# Power_conversion_board.net
KiCad netlist of a schematic drawn in EAGLE
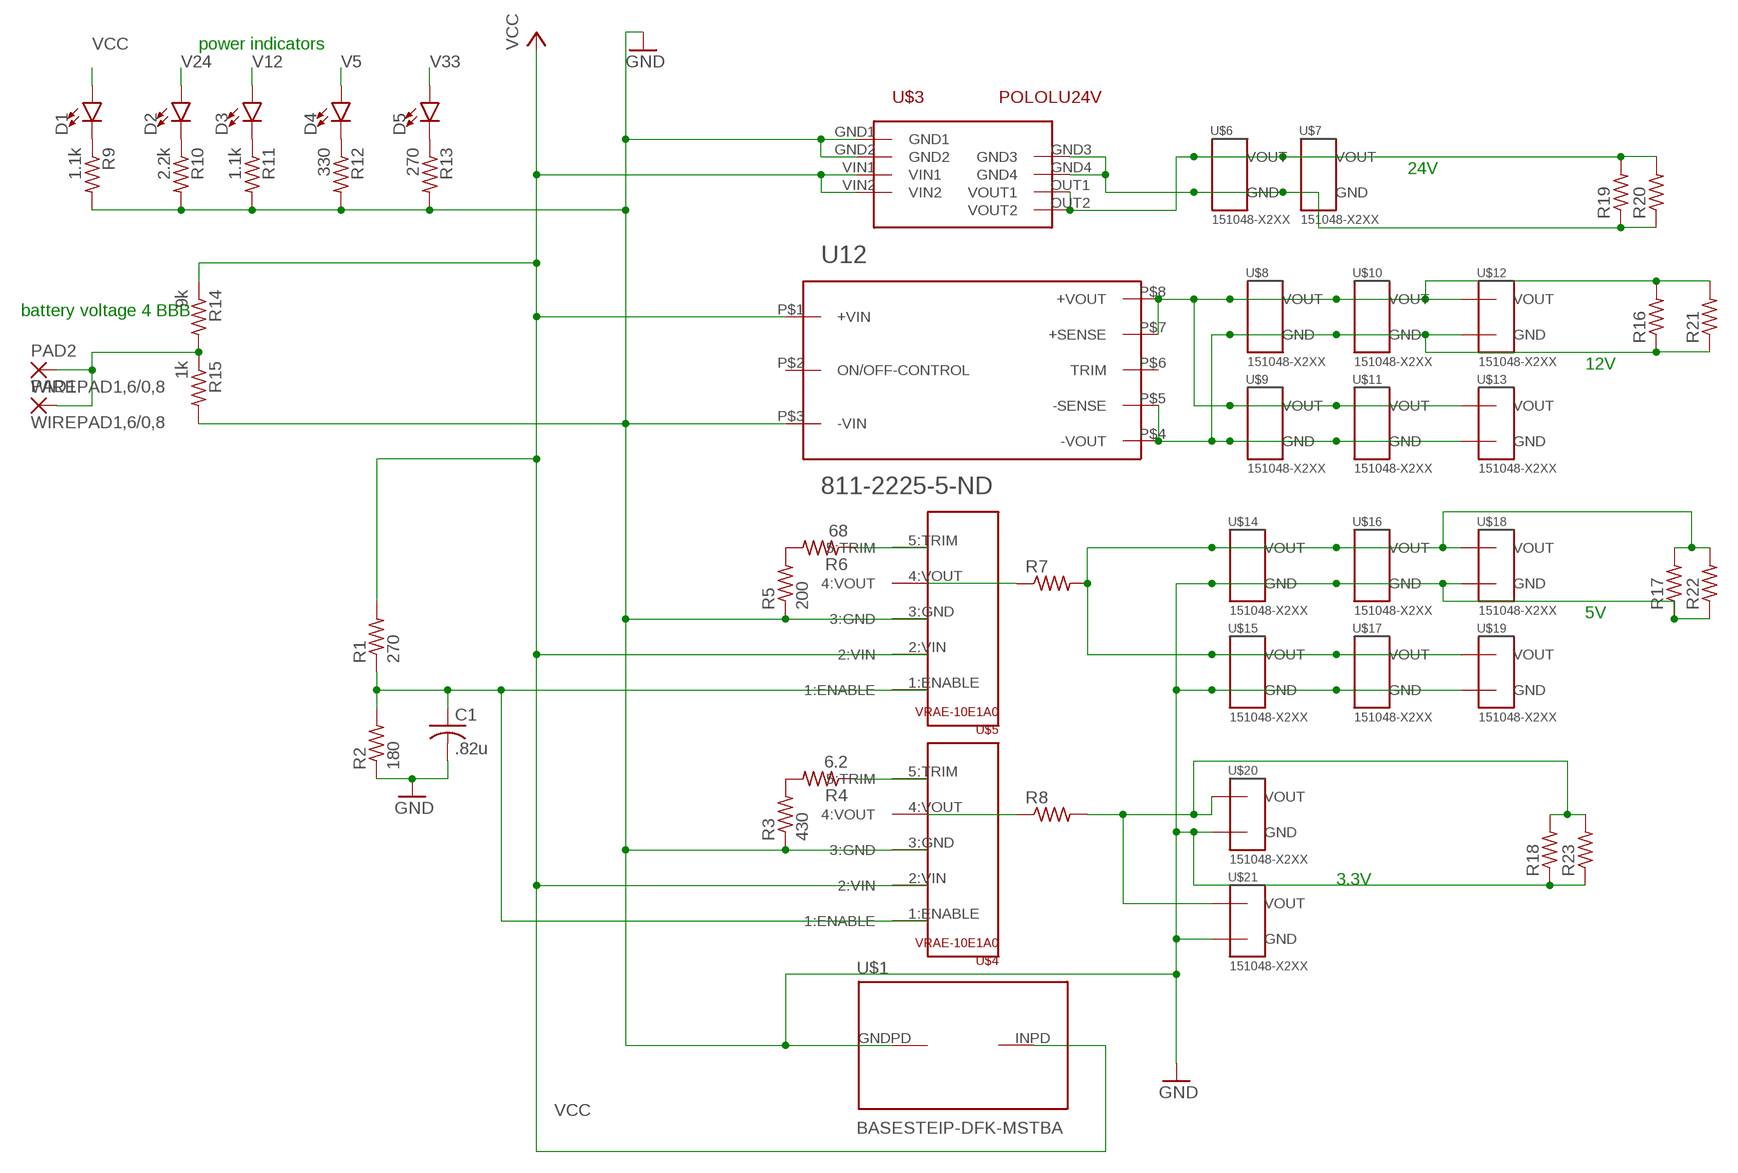
[diagram p0: schematic, sheet 1]

(export (version "E")
  (design (tool "Eeschema 10.0.6"))
  (components
    (comp (ref "C1")
      (value ".82u")
      (footprint "eagle-import:C0603")
      (libsource (lib "eagle-import") (part "C-USC0603"))
    )
    (comp (ref "D1")
      (value "LED5MM")
      (footprint "eagle-import:LED_5MM")
      (libsource (lib "eagle-import") (part "LED5MM"))
    )
    (comp (ref "D2")
      (value "LED5MM")
      (footprint "eagle-import:LED_5MM")
      (libsource (lib "eagle-import") (part "LED5MM"))
    )
    (comp (ref "D3")
      (value "LED5MM")
      (footprint "eagle-import:LED_5MM")
      (libsource (lib "eagle-import") (part "LED5MM"))
    )
    (comp (ref "D4")
      (value "LED5MM")
      (footprint "eagle-import:LED_5MM")
      (libsource (lib "eagle-import") (part "LED5MM"))
    )
    (comp (ref "D5")
      (value "LED5MM")
      (footprint "eagle-import:LED_5MM")
      (libsource (lib "eagle-import") (part "LED5MM"))
    )
    (comp (ref "PAD1")
      (value "WIREPAD1,6/0,8")
      (footprint "eagle-import:1,6_0,8")
      (libsource (lib "eagle-import") (part "WIREPAD1,6/0,8"))
    )
    (comp (ref "PAD2")
      (value "WIREPAD1,6/0,8")
      (footprint "eagle-import:1,6_0,8")
      (libsource (lib "eagle-import") (part "WIREPAD1,6/0,8"))
    )
    (comp (ref "R1")
      (value "270")
      (footprint "eagle-import:R0603")
      (libsource (lib "eagle-import") (part "resistor_R-US_R0603"))
    )
    (comp (ref "R2")
      (value "180")
      (footprint "eagle-import:R0603")
      (libsource (lib "eagle-import") (part "resistor_R-US_R0603"))
    )
    (comp (ref "R3")
      (value "430")
      (footprint "eagle-import:R0603")
      (libsource (lib "eagle-import") (part "resistor_R-US_R0603"))
    )
    (comp (ref "R4")
      (value "6.2")
      (footprint "eagle-import:R0603")
      (libsource (lib "eagle-import") (part "resistor_R-US_R0603"))
    )
    (comp (ref "R5")
      (value "200")
      (footprint "eagle-import:R0603")
      (libsource (lib "eagle-import") (part "resistor_R-US_R0603"))
    )
    (comp (ref "R6")
      (value "68")
      (footprint "eagle-import:R0603")
      (libsource (lib "eagle-import") (part "resistor_R-US_R0603"))
    )
    (comp (ref "R7")
      (value "R-US_0204/5")
      (footprint "eagle-import:00PTCPACKAGE")
      (libsource (lib "eagle-import") (part "R-US_0204/5"))
    )
    (comp (ref "R8")
      (value "R-US_0204/5")
      (footprint "eagle-import:00PTCPACKAGE")
      (libsource (lib "eagle-import") (part "R-US_0204/5"))
    )
    (comp (ref "R9")
      (value "1.1k")
      (footprint "eagle-import:R0603")
      (libsource (lib "eagle-import") (part "resistor_R-US_R0603"))
    )
    (comp (ref "R10")
      (value "2.2k")
      (footprint "eagle-import:R0603")
      (libsource (lib "eagle-import") (part "resistor_R-US_R0603"))
    )
    (comp (ref "R11")
      (value "1.1k")
      (footprint "eagle-import:R0603")
      (libsource (lib "eagle-import") (part "resistor_R-US_R0603"))
    )
    (comp (ref "R12")
      (value "330")
      (footprint "eagle-import:R0603")
      (libsource (lib "eagle-import") (part "resistor_R-US_R0603"))
    )
    (comp (ref "R13")
      (value "270")
      (footprint "eagle-import:R0603")
      (libsource (lib "eagle-import") (part "resistor_R-US_R0603"))
    )
    (comp (ref "R14")
      (value "9k")
      (footprint "eagle-import:R0603")
      (libsource (lib "eagle-import") (part "resistor_R-US_R0603"))
    )
    (comp (ref "R15")
      (value "1k")
      (footprint "eagle-import:R0603")
      (libsource (lib "eagle-import") (part "resistor_R-US_R0603"))
    )
    (comp (ref "R16")
      (value "R-US_0204/5")
      (footprint "eagle-import:00PTCPACKAGE")
      (libsource (lib "eagle-import") (part "R-US_0204/5"))
    )
    (comp (ref "R17")
      (value "R-US_0204/5")
      (footprint "eagle-import:00PTCPACKAGE")
      (libsource (lib "eagle-import") (part "R-US_0204/5"))
    )
    (comp (ref "R18")
      (value "R-US_0204/5")
      (footprint "eagle-import:00PTCPACKAGE")
      (libsource (lib "eagle-import") (part "R-US_0204/5"))
    )
    (comp (ref "R19")
      (value "R-US_0204/5")
      (footprint "eagle-import:00PTCPACKAGE")
      (libsource (lib "eagle-import") (part "R-US_0204/5"))
    )
    (comp (ref "R20")
      (value "R-US_0204/5")
      (footprint "eagle-import:00PTCPACKAGE")
      (libsource (lib "eagle-import") (part "R-US_0204/5"))
    )
    (comp (ref "R21")
      (value "R-US_0204/5")
      (footprint "eagle-import:00PTCPACKAGE")
      (libsource (lib "eagle-import") (part "R-US_0204/5"))
    )
    (comp (ref "R22")
      (value "R-US_0204/5")
      (footprint "eagle-import:00PTCPACKAGE")
      (libsource (lib "eagle-import") (part "R-US_0204/5"))
    )
    (comp (ref "R23")
      (value "R-US_0204/5")
      (footprint "eagle-import:00PTCPACKAGE")
      (libsource (lib "eagle-import") (part "R-US_0204/5"))
    )
    (comp (ref "U$1")
      (value "BASESTEIP-DFK-MSTBA")
      (footprint "eagle-import:BASESTRIP-DFK-MSTBA")
      (libsource (lib "eagle-import") (part "BASESTEIP-DFK-MSTBA"))
    )
    (comp (ref "U$3")
      (value "POLOLU24V")
      (footprint "eagle-import:POLOLU24")
      (libsource (lib "eagle-import") (part "POLOLU24V"))
    )
    (comp (ref "U$4")
      (value "VRAE-10E1A0")
      (footprint "eagle-import:BEL_VRAE-10E1A0")
      (libsource (lib "eagle-import") (part "VRAE-10E1A0"))
    )
    (comp (ref "U$5")
      (value "VRAE-10E1A0")
      (footprint "eagle-import:BEL_VRAE-10E1A0")
      (libsource (lib "eagle-import") (part "VRAE-10E1A0"))
    )
    (comp (ref "U$6")
      (value "151048-X2XX")
      (footprint "eagle-import:151048-X2XX")
      (libsource (lib "eagle-import") (part "151048-X2XX"))
    )
    (comp (ref "U$7")
      (value "151048-X2XX")
      (footprint "eagle-import:151048-X2XX")
      (libsource (lib "eagle-import") (part "151048-X2XX"))
    )
    (comp (ref "U$8")
      (value "151048-X2XX")
      (footprint "eagle-import:151048-X2XX")
      (libsource (lib "eagle-import") (part "151048-X2XX"))
    )
    (comp (ref "U$9")
      (value "151048-X2XX")
      (footprint "eagle-import:151048-X2XX")
      (libsource (lib "eagle-import") (part "151048-X2XX"))
    )
    (comp (ref "U$10")
      (value "151048-X2XX")
      (footprint "eagle-import:151048-X2XX")
      (libsource (lib "eagle-import") (part "151048-X2XX"))
    )
    (comp (ref "U$11")
      (value "151048-X2XX")
      (footprint "eagle-import:151048-X2XX")
      (libsource (lib "eagle-import") (part "151048-X2XX"))
    )
    (comp (ref "U$12")
      (value "151048-X2XX")
      (footprint "eagle-import:151048-X2XX")
      (libsource (lib "eagle-import") (part "151048-X2XX"))
    )
    (comp (ref "U$13")
      (value "151048-X2XX")
      (footprint "eagle-import:151048-X2XX")
      (libsource (lib "eagle-import") (part "151048-X2XX"))
    )
    (comp (ref "U$14")
      (value "151048-X2XX")
      (footprint "eagle-import:151048-X2XX")
      (libsource (lib "eagle-import") (part "151048-X2XX"))
    )
    (comp (ref "U$15")
      (value "151048-X2XX")
      (footprint "eagle-import:151048-X2XX")
      (libsource (lib "eagle-import") (part "151048-X2XX"))
    )
    (comp (ref "U$16")
      (value "151048-X2XX")
      (footprint "eagle-import:151048-X2XX")
      (libsource (lib "eagle-import") (part "151048-X2XX"))
    )
    (comp (ref "U$17")
      (value "151048-X2XX")
      (footprint "eagle-import:151048-X2XX")
      (libsource (lib "eagle-import") (part "151048-X2XX"))
    )
    (comp (ref "U$18")
      (value "151048-X2XX")
      (footprint "eagle-import:151048-X2XX")
      (libsource (lib "eagle-import") (part "151048-X2XX"))
    )
    (comp (ref "U$19")
      (value "151048-X2XX")
      (footprint "eagle-import:151048-X2XX")
      (libsource (lib "eagle-import") (part "151048-X2XX"))
    )
    (comp (ref "U$20")
      (value "151048-X2XX")
      (footprint "eagle-import:151048-X2XX")
      (libsource (lib "eagle-import") (part "151048-X2XX"))
    )
    (comp (ref "U$21")
      (value "151048-X2XX")
      (footprint "eagle-import:151048-X2XX")
      (libsource (lib "eagle-import") (part "151048-X2XX"))
    )
    (comp (ref "U12")
      (value "811-2225-5-ND")
      (footprint "eagle-import:811-2225-5-ND")
      (libsource (lib "eagle-import") (part "811-2225-5-ND"))
    )
  )
  (nets
    (net (code "1") (name "/V5") (class "Default")
      (node (ref "D4") (pin "A") (pinfunction "A_A") (pintype "passive"))
      (node (ref "R17") (pin "2") (pinfunction "2_2") (pintype "passive"))
      (node (ref "R22") (pin "2") (pinfunction "2_2") (pintype "passive"))
      (node (ref "R7") (pin "2") (pinfunction "2_2") (pintype "passive"))
      (node (ref "U$14") (pin "VOUT") (pinfunction "VOUT_VOUT") (pintype "bidirectional"))
      (node (ref "U$15") (pin "VOUT") (pinfunction "VOUT_VOUT") (pintype "bidirectional"))
      (node (ref "U$16") (pin "VOUT") (pinfunction "VOUT_VOUT") (pintype "bidirectional"))
      (node (ref "U$17") (pin "VOUT") (pinfunction "VOUT_VOUT") (pintype "bidirectional"))
      (node (ref "U$18") (pin "VOUT") (pinfunction "VOUT_VOUT") (pintype "bidirectional"))
      (node (ref "U$19") (pin "VOUT") (pinfunction "VOUT_VOUT") (pintype "bidirectional"))
    )
    (net (code "2") (name "/V12") (class "Default")
      (node (ref "D3") (pin "A") (pinfunction "A_A") (pintype "passive"))
      (node (ref "R16") (pin "2") (pinfunction "2_2") (pintype "passive"))
      (node (ref "R21") (pin "2") (pinfunction "2_2") (pintype "passive"))
      (node (ref "U$10") (pin "VOUT") (pinfunction "VOUT_VOUT") (pintype "bidirectional"))
      (node (ref "U$11") (pin "VOUT") (pinfunction "VOUT_VOUT") (pintype "bidirectional"))
      (node (ref "U$12") (pin "VOUT") (pinfunction "VOUT_VOUT") (pintype "bidirectional"))
      (node (ref "U$13") (pin "VOUT") (pinfunction "VOUT_VOUT") (pintype "bidirectional"))
      (node (ref "U$8") (pin "VOUT") (pinfunction "VOUT_VOUT") (pintype "bidirectional"))
      (node (ref "U$9") (pin "VOUT") (pinfunction "VOUT_VOUT") (pintype "bidirectional"))
      (node (ref "U12") (pin "P$7") (pinfunction "+SENSE_P$7") (pintype "bidirectional"))
      (node (ref "U12") (pin "P$8") (pinfunction "+VOUT_P$8") (pintype "bidirectional"))
    )
    (net (code "3") (name "/V24") (class "Default")
      (node (ref "D2") (pin "A") (pinfunction "A_A") (pintype "passive"))
      (node (ref "R19") (pin "2") (pinfunction "2_2") (pintype "passive"))
      (node (ref "R20") (pin "2") (pinfunction "2_2") (pintype "passive"))
      (node (ref "U$3") (pin "OUT1") (pinfunction "VOUT1_OUT1") (pintype "bidirectional"))
      (node (ref "U$3") (pin "OUT2") (pinfunction "VOUT2_OUT2") (pintype "bidirectional"))
      (node (ref "U$6") (pin "VOUT") (pinfunction "VOUT_VOUT") (pintype "bidirectional"))
      (node (ref "U$7") (pin "VOUT") (pinfunction "VOUT_VOUT") (pintype "bidirectional"))
    )
    (net (code "4") (name "/V33") (class "Default")
      (node (ref "D5") (pin "A") (pinfunction "A_A") (pintype "passive"))
      (node (ref "R18") (pin "2") (pinfunction "2_2") (pintype "passive"))
      (node (ref "R23") (pin "2") (pinfunction "2_2") (pintype "passive"))
      (node (ref "R8") (pin "2") (pinfunction "2_2") (pintype "passive"))
      (node (ref "U$20") (pin "VOUT") (pinfunction "VOUT_VOUT") (pintype "bidirectional"))
      (node (ref "U$21") (pin "VOUT") (pinfunction "VOUT_VOUT") (pintype "bidirectional"))
    )
    (net (code "5") (name "GND") (class "Default")
      (node (ref "C1") (pin "2") (pinfunction "2_2") (pintype "passive"))
      (node (ref "R10") (pin "2") (pinfunction "2_2") (pintype "passive"))
      (node (ref "R11") (pin "2") (pinfunction "2_2") (pintype "passive"))
      (node (ref "R12") (pin "2") (pinfunction "2_2") (pintype "passive"))
      (node (ref "R13") (pin "2") (pinfunction "2_2") (pintype "passive"))
      (node (ref "R15") (pin "2") (pinfunction "2_2") (pintype "passive"))
      (node (ref "R16") (pin "1") (pinfunction "1_1") (pintype "passive"))
      (node (ref "R17") (pin "1") (pinfunction "1_1") (pintype "passive"))
      (node (ref "R18") (pin "1") (pinfunction "1_1") (pintype "passive"))
      (node (ref "R19") (pin "1") (pinfunction "1_1") (pintype "passive"))
      (node (ref "R2") (pin "1") (pinfunction "1_1") (pintype "passive"))
      (node (ref "R20") (pin "1") (pinfunction "1_1") (pintype "passive"))
      (node (ref "R21") (pin "1") (pinfunction "1_1") (pintype "passive"))
      (node (ref "R22") (pin "1") (pinfunction "1_1") (pintype "passive"))
      (node (ref "R23") (pin "1") (pinfunction "1_1") (pintype "passive"))
      (node (ref "R3") (pin "1") (pinfunction "1_1") (pintype "passive"))
      (node (ref "R5") (pin "1") (pinfunction "1_1") (pintype "passive"))
      (node (ref "R9") (pin "2") (pinfunction "2_2") (pintype "passive"))
      (node (ref "U$1") (pin "GNDPD") (pinfunction "GNDPD_GNDPD") (pintype "bidirectional"))
      (node (ref "U$10") (pin "GND") (pinfunction "GND_GND") (pintype "bidirectional"))
      (node (ref "U$11") (pin "GND") (pinfunction "GND_GND") (pintype "bidirectional"))
      (node (ref "U$12") (pin "GND") (pinfunction "GND_GND") (pintype "bidirectional"))
      (node (ref "U$13") (pin "GND") (pinfunction "GND_GND") (pintype "bidirectional"))
      (node (ref "U$14") (pin "GND") (pinfunction "GND_GND") (pintype "bidirectional"))
      (node (ref "U$15") (pin "GND") (pinfunction "GND_GND") (pintype "bidirectional"))
      (node (ref "U$16") (pin "GND") (pinfunction "GND_GND") (pintype "bidirectional"))
      (node (ref "U$17") (pin "GND") (pinfunction "GND_GND") (pintype "bidirectional"))
      (node (ref "U$18") (pin "GND") (pinfunction "GND_GND") (pintype "bidirectional"))
      (node (ref "U$19") (pin "GND") (pinfunction "GND_GND") (pintype "bidirectional"))
      (node (ref "U$20") (pin "GND") (pinfunction "GND_GND") (pintype "bidirectional"))
      (node (ref "U$21") (pin "GND") (pinfunction "GND_GND") (pintype "bidirectional"))
      (node (ref "U$3") (pin "GND1") (pinfunction "GND1_GND1") (pintype "bidirectional"))
      (node (ref "U$3") (pin "GND2") (pinfunction "GND2_GND2") (pintype "bidirectional"))
      (node (ref "U$3") (pin "GND3") (pinfunction "GND3_GND3") (pintype "bidirectional"))
      (node (ref "U$3") (pin "GND4") (pinfunction "GND4_GND4") (pintype "bidirectional"))
      (node (ref "U$4") (pin "3:GND") (pinfunction "3:GND_3:GND") (pintype "bidirectional"))
      (node (ref "U$5") (pin "3:GND") (pinfunction "3:GND_3:GND") (pintype "bidirectional"))
      (node (ref "U$6") (pin "GND") (pinfunction "GND_GND") (pintype "bidirectional"))
      (node (ref "U$7") (pin "GND") (pinfunction "GND_GND") (pintype "bidirectional"))
      (node (ref "U$8") (pin "GND") (pinfunction "GND_GND") (pintype "bidirectional"))
      (node (ref "U$9") (pin "GND") (pinfunction "GND_GND") (pintype "bidirectional"))
      (node (ref "U12") (pin "P$3") (pinfunction "-VIN_P$3") (pintype "bidirectional"))
      (node (ref "U12") (pin "P$4") (pinfunction "-VOUT_P$4") (pintype "bidirectional"))
      (node (ref "U12") (pin "P$5") (pinfunction "-SENSE_P$5") (pintype "bidirectional"))
    )
    (net (code "6") (name "Net-(C1-Pad1)") (class "Default")
      (node (ref "C1") (pin "1") (pinfunction "1_1") (pintype "passive"))
      (node (ref "R1") (pin "1") (pinfunction "1_1") (pintype "passive"))
      (node (ref "R2") (pin "2") (pinfunction "2_2") (pintype "passive"))
      (node (ref "U$4") (pin "1:ENABLE") (pinfunction "1:ENABLE_1:ENABLE") (pintype "input"))
      (node (ref "U$5") (pin "1:ENABLE") (pinfunction "1:ENABLE_1:ENABLE") (pintype "input"))
    )
    (net (code "7") (name "Net-(D1-C)") (class "Default")
      (node (ref "D1") (pin "K") (pinfunction "C_K") (pintype "passive"))
      (node (ref "R9") (pin "1") (pinfunction "1_1") (pintype "passive"))
    )
    (net (code "8") (name "Net-(D2-C)") (class "Default")
      (node (ref "D2") (pin "K") (pinfunction "C_K") (pintype "passive"))
      (node (ref "R10") (pin "1") (pinfunction "1_1") (pintype "passive"))
    )
    (net (code "9") (name "Net-(D3-C)") (class "Default")
      (node (ref "D3") (pin "K") (pinfunction "C_K") (pintype "passive"))
      (node (ref "R11") (pin "1") (pinfunction "1_1") (pintype "passive"))
    )
    (net (code "10") (name "Net-(D4-C)") (class "Default")
      (node (ref "D4") (pin "K") (pinfunction "C_K") (pintype "passive"))
      (node (ref "R12") (pin "1") (pinfunction "1_1") (pintype "passive"))
    )
    (net (code "11") (name "Net-(D5-C)") (class "Default")
      (node (ref "D5") (pin "K") (pinfunction "C_K") (pintype "passive"))
      (node (ref "R13") (pin "1") (pinfunction "1_1") (pintype "passive"))
    )
    (net (code "12") (name "Net-(PAD1-P)") (class "Default")
      (node (ref "PAD1") (pin "1") (pinfunction "P_1") (pintype "passive"))
      (node (ref "PAD2") (pin "1") (pinfunction "P_1") (pintype "passive"))
      (node (ref "R14") (pin "2") (pinfunction "2_2") (pintype "passive"))
      (node (ref "R15") (pin "1") (pinfunction "1_1") (pintype "passive"))
    )
    (net (code "13") (name "Net-(R3-Pad2)") (class "Default")
      (node (ref "R3") (pin "2") (pinfunction "2_2") (pintype "passive"))
      (node (ref "R4") (pin "2") (pinfunction "2_2") (pintype "passive"))
    )
    (net (code "14") (name "Net-(R4-Pad1)") (class "Default")
      (node (ref "R4") (pin "1") (pinfunction "1_1") (pintype "passive"))
      (node (ref "U$4") (pin "5:TRIM") (pinfunction "5:TRIM_5:TRIM") (pintype "bidirectional"))
    )
    (net (code "15") (name "Net-(R5-Pad2)") (class "Default")
      (node (ref "R5") (pin "2") (pinfunction "2_2") (pintype "passive"))
      (node (ref "R6") (pin "2") (pinfunction "2_2") (pintype "passive"))
    )
    (net (code "16") (name "Net-(R6-Pad1)") (class "Default")
      (node (ref "R6") (pin "1") (pinfunction "1_1") (pintype "passive"))
      (node (ref "U$5") (pin "5:TRIM") (pinfunction "5:TRIM_5:TRIM") (pintype "bidirectional"))
    )
    (net (code "17") (name "Net-(R7-Pad1)") (class "Default")
      (node (ref "R7") (pin "1") (pinfunction "1_1") (pintype "passive"))
      (node (ref "U$5") (pin "4:VOUT") (pinfunction "4:VOUT_4:VOUT") (pintype "output"))
    )
    (net (code "18") (name "Net-(R8-Pad1)") (class "Default")
      (node (ref "R8") (pin "1") (pinfunction "1_1") (pintype "passive"))
      (node (ref "U$4") (pin "4:VOUT") (pinfunction "4:VOUT_4:VOUT") (pintype "output"))
    )
    (net (code "19") (name "VCC") (class "Default")
      (node (ref "D1") (pin "A") (pinfunction "A_A") (pintype "passive"))
      (node (ref "R1") (pin "2") (pinfunction "2_2") (pintype "passive"))
      (node (ref "R14") (pin "1") (pinfunction "1_1") (pintype "passive"))
      (node (ref "U$1") (pin "INPD") (pinfunction "INPD_INPD") (pintype "bidirectional"))
      (node (ref "U$3") (pin "VIN1") (pinfunction "VIN1_VIN1") (pintype "bidirectional"))
      (node (ref "U$3") (pin "VIN2") (pinfunction "VIN2_VIN2") (pintype "bidirectional"))
      (node (ref "U$4") (pin "2:VIN") (pinfunction "2:VIN_2:VIN") (pintype "input"))
      (node (ref "U$5") (pin "2:VIN") (pinfunction "2:VIN_2:VIN") (pintype "input"))
      (node (ref "U12") (pin "P$1") (pinfunction "+VIN_P$1") (pintype "bidirectional"))
    )
    (net (code "20") (name "unconnected-(U12-ON{slash}OFF-CONTROL-PadP$2)") (class "Default")
      (node (ref "U12") (pin "P$2") (pinfunction "ON/OFF-CONTROL_P$2") (pintype "bidirectional"))
    )
    (net (code "21") (name "unconnected-(U12-TRIM-PadP$6)") (class "Default")
      (node (ref "U12") (pin "P$6") (pinfunction "TRIM_P$6") (pintype "bidirectional"))
    )
  )
)
